# main.net
KiCad netlist of a schematic drawn in EAGLE
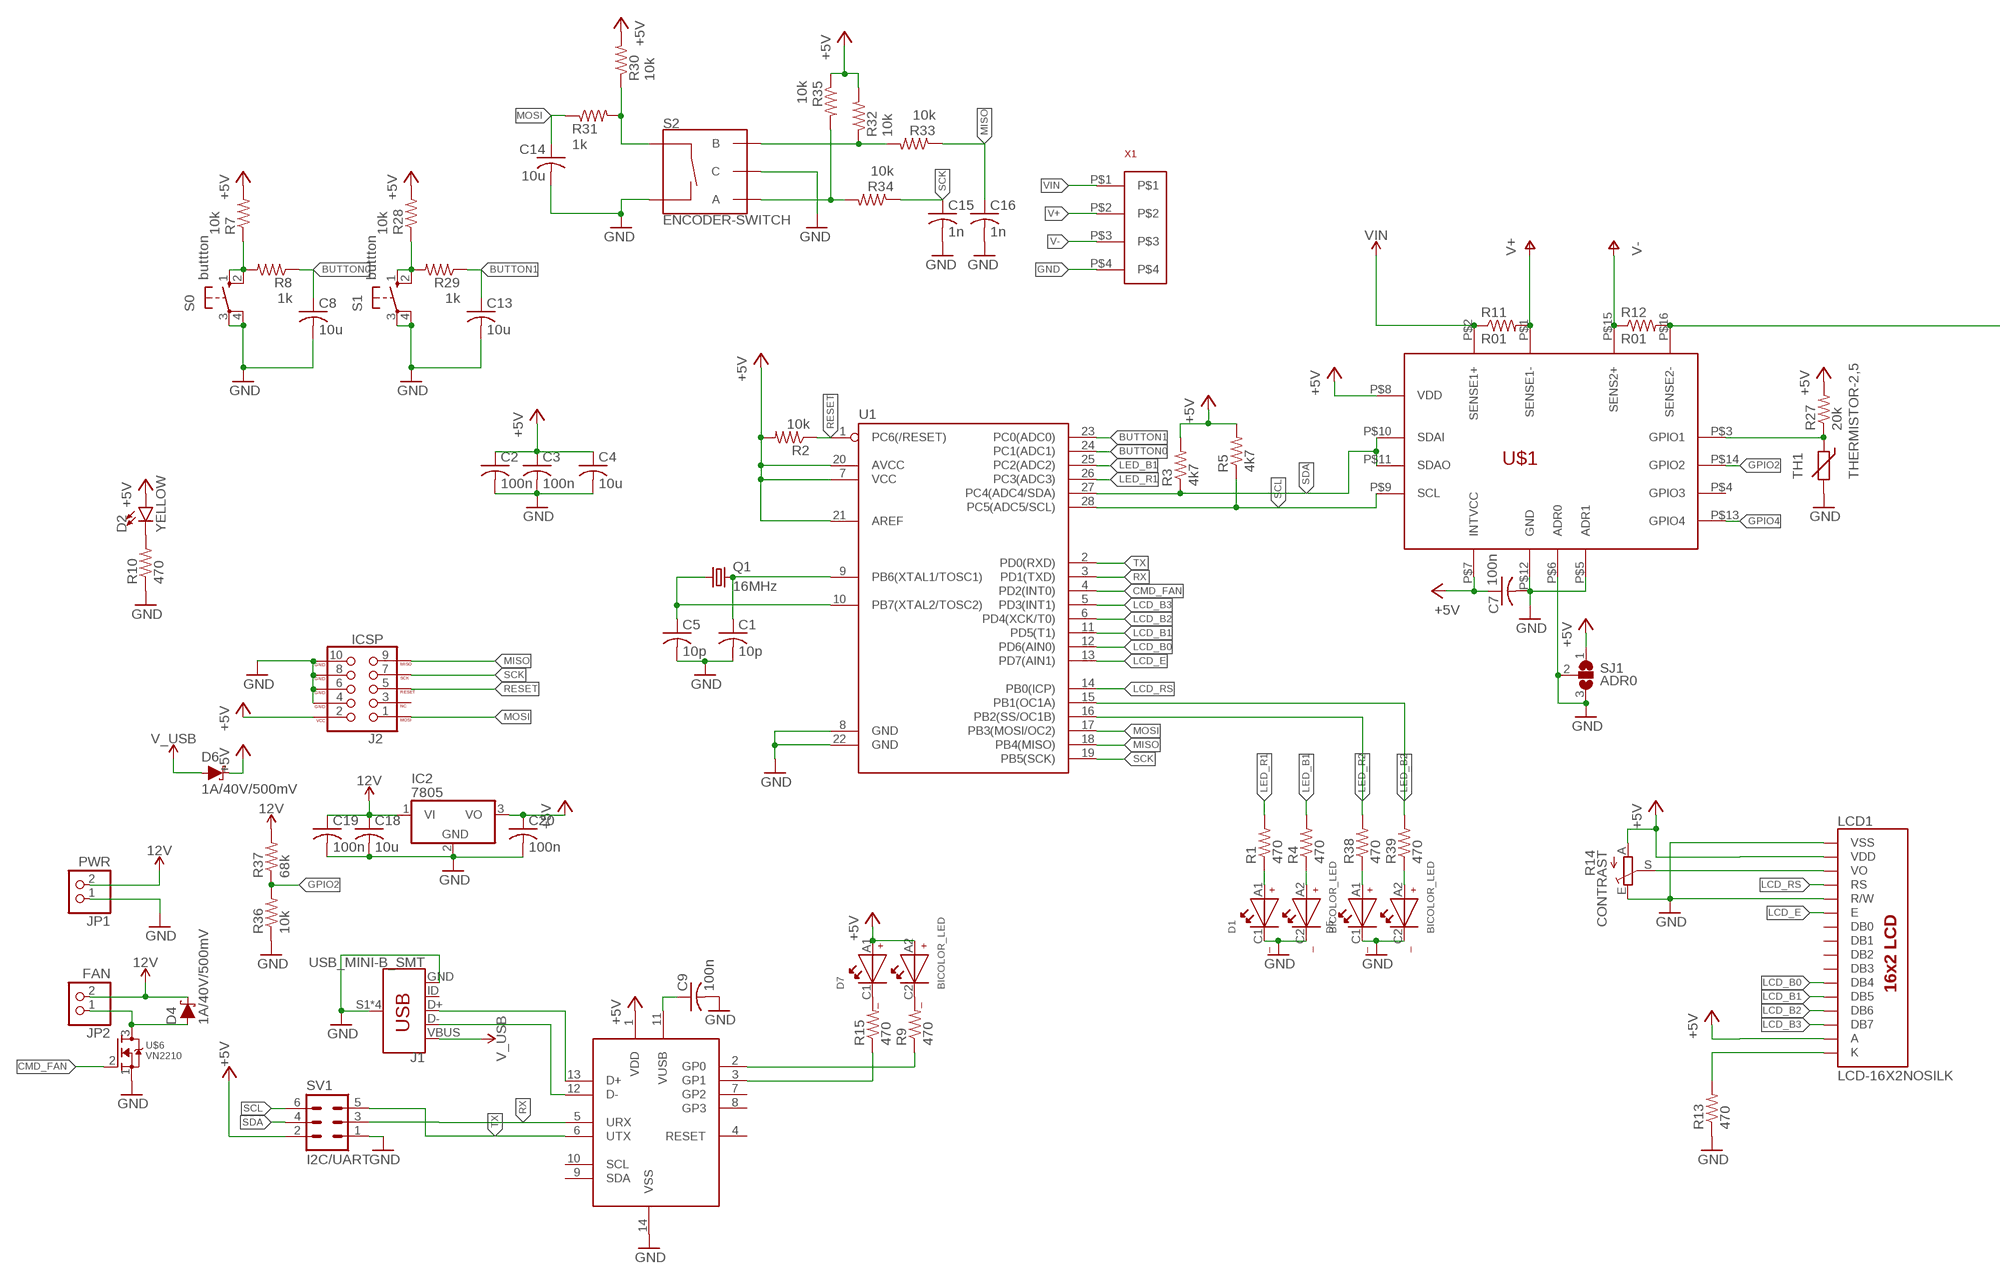
[diagram p0: schematic, sheet 1, part 1 of 2]
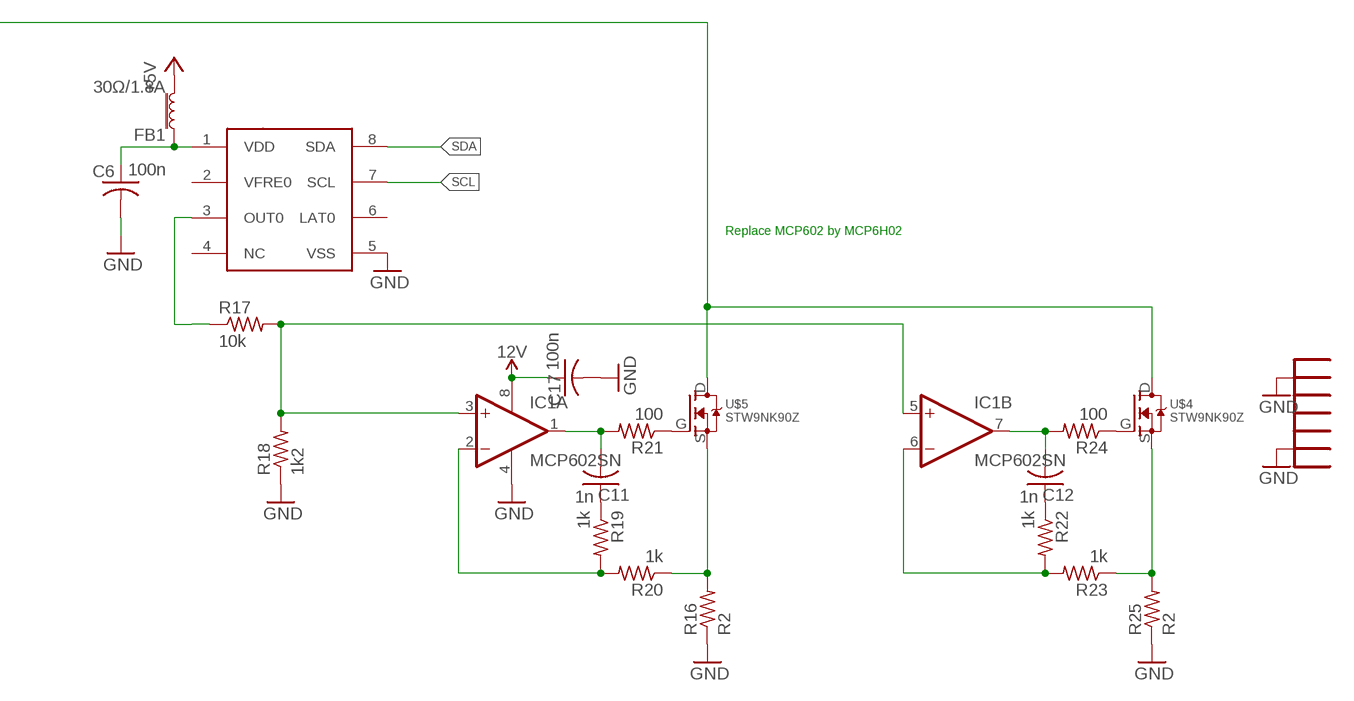
[diagram p1: schematic, sheet 1, part 2 of 2]

(export (version "E")
  (design (tool "Eeschema 10.0.6"))
  (components
    (comp (ref "BR1")
      (value "MCP2221A")
      (footprint "eagle-import:DIP14")
      (libsource (lib "eagle-import") (part "MCP2221A"))
    )
    (comp (ref "C1")
      (value "10p")
      (footprint "eagle-import:C0603")
      (libsource (lib "eagle-import") (part "C-USC0603"))
    )
    (comp (ref "C2")
      (value "100n")
      (footprint "eagle-import:C0603")
      (libsource (lib "eagle-import") (part "C-USC0603"))
    )
    (comp (ref "C3")
      (value "100n")
      (footprint "eagle-import:C0603")
      (libsource (lib "eagle-import") (part "C-USC0603"))
    )
    (comp (ref "C4")
      (value "10u")
      (footprint "eagle-import:C1206")
      (libsource (lib "eagle-import") (part "C-USC1206"))
    )
    (comp (ref "C5")
      (value "10p")
      (footprint "eagle-import:C0603")
      (libsource (lib "eagle-import") (part "C-USC0603"))
    )
    (comp (ref "C6")
      (value "100n")
      (footprint "eagle-import:C0603")
      (libsource (lib "eagle-import") (part "C-USC0603"))
    )
    (comp (ref "C7")
      (value "100n")
      (footprint "eagle-import:C0603")
      (libsource (lib "eagle-import") (part "C-USC0603"))
    )
    (comp (ref "C8")
      (value "10u")
      (footprint "eagle-import:C0603")
      (libsource (lib "eagle-import") (part "C-USC0603"))
    )
    (comp (ref "C9")
      (value "100n")
      (footprint "eagle-import:C0603")
      (libsource (lib "eagle-import") (part "C-USC0603"))
    )
    (comp (ref "C11")
      (value "1n")
      (footprint "eagle-import:C0805")
      (libsource (lib "eagle-import") (part "C-USC0805"))
    )
    (comp (ref "C12")
      (value "1n")
      (footprint "eagle-import:C0805")
      (libsource (lib "eagle-import") (part "C-USC0805"))
    )
    (comp (ref "C13")
      (value "10u")
      (footprint "eagle-import:C0603")
      (libsource (lib "eagle-import") (part "C-USC0603"))
    )
    (comp (ref "C14")
      (value "10u")
      (footprint "eagle-import:C0603")
      (libsource (lib "eagle-import") (part "C-USC0603"))
    )
    (comp (ref "C15")
      (value "1n")
      (footprint "eagle-import:C0603")
      (libsource (lib "eagle-import") (part "C-USC0603"))
    )
    (comp (ref "C16")
      (value "1n")
      (footprint "eagle-import:C0603")
      (libsource (lib "eagle-import") (part "C-USC0603"))
    )
    (comp (ref "C17")
      (value "100n")
      (footprint "eagle-import:C0603")
      (libsource (lib "eagle-import") (part "C-USC0603"))
    )
    (comp (ref "C18")
      (value "10u")
      (footprint "eagle-import:C1206")
      (libsource (lib "eagle-import") (part "C-USC1206"))
    )
    (comp (ref "C19")
      (value "100n")
      (footprint "eagle-import:C0603")
      (libsource (lib "eagle-import") (part "C-USC0603"))
    )
    (comp (ref "C20")
      (value "100n")
      (footprint "eagle-import:C0603")
      (libsource (lib "eagle-import") (part "C-USC0603"))
    )
    (comp (ref "D1")
      (value "BICOLOR_LED")
      (footprint "eagle-import:BICOLOR_LED")
      (libsource (lib "eagle-import") (part "BICOLOR_LED"))
    )
    (comp (ref "D2")
      (value "YELLOW")
      (footprint "eagle-import:LED_3MM")
      (libsource (lib "eagle-import") (part "LED3MM"))
    )
    (comp (ref "D4")
      (value "1A/40V/500mV")
      (footprint "eagle-import:SMA-DIODE")
      (libsource (lib "eagle-import") (part "DIODE-SCHOTTKY-SS14"))
    )
    (comp (ref "D5")
      (value "BICOLOR_LED")
      (footprint "eagle-import:BICOLOR_LED")
      (libsource (lib "eagle-import") (part "BICOLOR_LED"))
    )
    (comp (ref "D6")
      (value "1A/40V/500mV")
      (footprint "eagle-import:SMA-DIODE")
      (libsource (lib "eagle-import") (part "DIODE-SCHOTTKY-SS14"))
    )
    (comp (ref "D7")
      (value "BICOLOR_LED")
      (footprint "eagle-import:BICOLOR_LED")
      (libsource (lib "eagle-import") (part "BICOLOR_LED"))
    )
    (comp (ref "FB1")
      (value "30Ω/1.8A")
      (footprint "eagle-import:0603")
      (libsource (lib "eagle-import") (part "FERRITE_BEAD-0603"))
    )
    (comp (ref "IC1")
      (value "MCP602SN")
      (footprint "eagle-import:SO08")
      (libsource (lib "eagle-import") (part "MCP602SN"))
    )
    (comp (ref "IC2")
      (value "7805")
      (footprint "eagle-import:TO220V")
      (libsource (lib "eagle-import") (part "78TV6"))
    )
    (comp (ref "J1")
      (value "USB_MINI-B_SMT")
      (footprint "eagle-import:USB-MINIB")
      (libsource (lib "eagle-import") (part "USB_MINI-B_SMT"))
    )
    (comp (ref "J2")
      (value "ICSP")
      (footprint "eagle-import:2X5-SHROUDED")
      (libsource (lib "eagle-import") (part "AVR_SPI_PROG_5X2PTH2"))
    )
    (comp (ref "JP1")
      (value "PWR")
      (footprint "eagle-import:1X02")
      (libsource (lib "eagle-import") (part "PINHD-1X2"))
    )
    (comp (ref "JP2")
      (value "FAN")
      (footprint "eagle-import:1X02")
      (libsource (lib "eagle-import") (part "PINHD-1X2"))
    )
    (comp (ref "LCD1")
      (value "LCD-16X2NOSILK")
      (footprint "eagle-import:LCD-16X2_NOSILK")
      (libsource (lib "eagle-import") (part "LCD-16X2NOSILK"))
    )
    (comp (ref "Q1")
      (value "16MHz")
      (footprint "eagle-import:HC49U70")
      (libsource (lib "eagle-import") (part "CRYSTALHC49U70"))
    )
    (comp (ref "R1")
      (value "470")
      (footprint "eagle-import:R0805")
      (libsource (lib "eagle-import") (part "R-US_R0805"))
    )
    (comp (ref "R2")
      (value "10k")
      (footprint "eagle-import:R0805")
      (libsource (lib "eagle-import") (part "R-US_R0805"))
    )
    (comp (ref "R3")
      (value "4k7")
      (footprint "eagle-import:R0805")
      (libsource (lib "eagle-import") (part "R-US_R0805"))
    )
    (comp (ref "R4")
      (value "470")
      (footprint "eagle-import:R0805")
      (libsource (lib "eagle-import") (part "R-US_R0805"))
    )
    (comp (ref "R5")
      (value "4k7")
      (footprint "eagle-import:R0805")
      (libsource (lib "eagle-import") (part "R-US_R0805"))
    )
    (comp (ref "R7")
      (value "10k")
      (footprint "eagle-import:R0805")
      (libsource (lib "eagle-import") (part "R-US_R0805"))
    )
    (comp (ref "R8")
      (value "1k")
      (footprint "eagle-import:R0805")
      (libsource (lib "eagle-import") (part "R-US_R0805"))
    )
    (comp (ref "R9")
      (value "470")
      (footprint "eagle-import:R0805")
      (libsource (lib "eagle-import") (part "R-US_R0805"))
    )
    (comp (ref "R10")
      (value "470")
      (footprint "eagle-import:R0805")
      (libsource (lib "eagle-import") (part "R-US_R0805"))
    )
    (comp (ref "R11")
      (value "R01")
      (footprint "eagle-import:R2512")
      (libsource (lib "eagle-import") (part "R-US_R2512"))
    )
    (comp (ref "R12")
      (value "R01")
      (footprint "eagle-import:R2512")
      (libsource (lib "eagle-import") (part "R-US_R2512"))
    )
    (comp (ref "R13")
      (value "470")
      (footprint "eagle-import:R0805")
      (libsource (lib "eagle-import") (part "R-US_R0805"))
    )
    (comp (ref "R14")
      (value "CONTRAST")
      (footprint "eagle-import:RJ9W")
      (libsource (lib "eagle-import") (part "TRIM_EU-RJ9W"))
    )
    (comp (ref "R15")
      (value "470")
      (footprint "eagle-import:R0805")
      (libsource (lib "eagle-import") (part "R-US_R0805"))
    )
    (comp (ref "R16")
      (value "R2")
      (footprint "eagle-import:R2512")
      (libsource (lib "eagle-import") (part "R-US_R2512"))
    )
    (comp (ref "R17")
      (value "10k")
      (footprint "eagle-import:R0805")
      (libsource (lib "eagle-import") (part "R-US_R0805"))
    )
    (comp (ref "R18")
      (value "1k2")
      (footprint "eagle-import:R0805")
      (libsource (lib "eagle-import") (part "R-US_R0805"))
    )
    (comp (ref "R19")
      (value "1k")
      (footprint "eagle-import:R0805")
      (libsource (lib "eagle-import") (part "R-US_R0805"))
    )
    (comp (ref "R20")
      (value "1k")
      (footprint "eagle-import:R0805")
      (libsource (lib "eagle-import") (part "R-US_R0805"))
    )
    (comp (ref "R21")
      (value "100")
      (footprint "eagle-import:R0805")
      (libsource (lib "eagle-import") (part "R-US_R0805"))
    )
    (comp (ref "R22")
      (value "1k")
      (footprint "eagle-import:R0805")
      (libsource (lib "eagle-import") (part "R-US_R0805"))
    )
    (comp (ref "R23")
      (value "1k")
      (footprint "eagle-import:R0805")
      (libsource (lib "eagle-import") (part "R-US_R0805"))
    )
    (comp (ref "R24")
      (value "100")
      (footprint "eagle-import:R0805")
      (libsource (lib "eagle-import") (part "R-US_R0805"))
    )
    (comp (ref "R25")
      (value "R2")
      (footprint "eagle-import:R2512")
      (libsource (lib "eagle-import") (part "R-US_R2512"))
    )
    (comp (ref "R27")
      (value "20k")
      (footprint "eagle-import:R0805")
      (libsource (lib "eagle-import") (part "R-US_R0805"))
    )
    (comp (ref "R28")
      (value "10k")
      (footprint "eagle-import:R0805")
      (libsource (lib "eagle-import") (part "R-US_R0805"))
    )
    (comp (ref "R29")
      (value "1k")
      (footprint "eagle-import:R0805")
      (libsource (lib "eagle-import") (part "R-US_R0805"))
    )
    (comp (ref "R30")
      (value "10k")
      (footprint "eagle-import:R0805")
      (libsource (lib "eagle-import") (part "R-US_R0805"))
    )
    (comp (ref "R31")
      (value "1k")
      (footprint "eagle-import:R0805")
      (libsource (lib "eagle-import") (part "R-US_R0805"))
    )
    (comp (ref "R32")
      (value "10k")
      (footprint "eagle-import:R0805")
      (libsource (lib "eagle-import") (part "R-US_R0805"))
    )
    (comp (ref "R33")
      (value "10k")
      (footprint "eagle-import:R0805")
      (libsource (lib "eagle-import") (part "R-US_R0805"))
    )
    (comp (ref "R34")
      (value "10k")
      (footprint "eagle-import:R0805")
      (libsource (lib "eagle-import") (part "R-US_R0805"))
    )
    (comp (ref "R35")
      (value "10k")
      (footprint "eagle-import:R0805")
      (libsource (lib "eagle-import") (part "R-US_R0805"))
    )
    (comp (ref "R36")
      (value "10k")
      (footprint "eagle-import:R0805")
      (libsource (lib "eagle-import") (part "R-US_R0805"))
    )
    (comp (ref "R37")
      (value "68k")
      (footprint "eagle-import:R0805")
      (libsource (lib "eagle-import") (part "R-US_R0805"))
    )
    (comp (ref "R38")
      (value "470")
      (footprint "eagle-import:R0805")
      (libsource (lib "eagle-import") (part "R-US_R0805"))
    )
    (comp (ref "R39")
      (value "470")
      (footprint "eagle-import:R0805")
      (libsource (lib "eagle-import") (part "R-US_R0805"))
    )
    (comp (ref "S0")
      (value "buttton")
      (footprint "eagle-import:B3F-10XX")
      (fields (field (name "MPN") "B3F-1000"))
      (libsource (lib "eagle-import") (part "10-XX"))
    )
    (comp (ref "S1")
      (value "buttton")
      (footprint "eagle-import:B3F-10XX")
      (fields (field (name "MPN") "B3F-1000"))
      (libsource (lib "eagle-import") (part "10-XX"))
    )
    (comp (ref "S2")
      (value "ENCODER-SWITCH")
      (footprint "eagle-import:ROTARY_ENC_PLAIN")
      (libsource (lib "eagle-import") (part "ENCODER-SWITCH"))
    )
    (comp (ref "SJ1")
      (value "ADR0")
      (footprint "eagle-import:SJ_2")
      (libsource (lib "eagle-import") (part "SJ2W"))
    )
    (comp (ref "SV1")
      (value "I2C/UART")
      (footprint "eagle-import:MA03-2")
      (libsource (lib "eagle-import") (part "MA03-2"))
    )
    (comp (ref "TH1")
      (value "THERMISTOR-2,5")
      (footprint "eagle-import:RS-2,5")
      (libsource (lib "eagle-import") (part "THERMISTOR-2,5"))
    )
    (comp (ref "U$1")
      (value "LTC2992")
      (footprint "eagle-import:MSOP16")
      (libsource (lib "eagle-import") (part "LTC2992"))
    )
    (comp (ref "U$2")
      (value "HEATSINK_0NOSILK")
      (footprint "eagle-import:HEATSINK_01")
      (libsource (lib "eagle-import") (part "HEATSINK_0NOSILK"))
    )
    (comp (ref "U$3")
      (value "MCP47FEB21")
      (footprint "eagle-import:TSSOP8")
      (libsource (lib "eagle-import") (part "MCP47FEB21"))
    )
    (comp (ref "U$4")
      (value "STW9NK90Z")
      (footprint "eagle-import:TO247BV")
      (libsource (lib "eagle-import") (part "STW9NK90Z"))
    )
    (comp (ref "U$5")
      (value "STW9NK90Z")
      (footprint "eagle-import:TO247BV")
      (libsource (lib "eagle-import") (part "STW9NK90Z"))
    )
    (comp (ref "U$6")
      (value "VN2210")
      (footprint "eagle-import:TO92")
      (libsource (lib "eagle-import") (part "VN2210"))
    )
    (comp (ref "U1")
      (value "328P")
      (footprint "eagle-import:DIP28")
      (libsource (lib "eagle-import") (part "ATMEGA328P_PDIP"))
    )
    (comp (ref "X1")
      (value "SCREWTERM_5MM_4WAY")
      (footprint "eagle-import:SCREWTERM_5MM_4WAY")
      (libsource (lib "eagle-import") (part "SCREWTERM_5MM_4WAY"))
    )
  )
  (nets
    (net (code "1") (name "+5V") (class "Default")
      (node (ref "BR1") (pin "1") (pinfunction "VDD_1") (pintype "bidirectional"))
      (node (ref "C2") (pin "1") (pinfunction "1_1") (pintype "passive"))
      (node (ref "C20") (pin "1") (pinfunction "1_1") (pintype "passive"))
      (node (ref "C3") (pin "1") (pinfunction "1_1") (pintype "passive"))
      (node (ref "C4") (pin "1") (pinfunction "1_1") (pintype "passive"))
      (node (ref "C7") (pin "1") (pinfunction "1_1") (pintype "passive"))
      (node (ref "D2") (pin "A") (pinfunction "A_A") (pintype "passive"))
      (node (ref "D6") (pin "C") (pinfunction "C_C") (pintype "passive"))
      (node (ref "D7") (pin "A1") (pinfunction "A1_A1") (pintype "passive"))
      (node (ref "D7") (pin "A2") (pinfunction "A2_A2") (pintype "passive"))
      (node (ref "FB1") (pin "2") (pinfunction "2_2") (pintype "passive"))
      (node (ref "IC2") (pin "3") (pinfunction "VO_3") (pintype "passive"))
      (node (ref "J2") (pin "2") (pinfunction "VCC_2") (pintype "power_in"))
      (node (ref "LCD1") (pin "15") (pinfunction "A_15") (pintype "power_in"))
      (node (ref "LCD1") (pin "2") (pinfunction "VDD_2") (pintype "power_in"))
      (node (ref "R14") (pin "A") (pinfunction "A_A") (pintype "passive"))
      (node (ref "R2") (pin "2") (pinfunction "2_2") (pintype "passive"))
      (node (ref "R27") (pin "2") (pinfunction "2_2") (pintype "passive"))
      (node (ref "R28") (pin "2") (pinfunction "2_2") (pintype "passive"))
      (node (ref "R3") (pin "2") (pinfunction "2_2") (pintype "passive"))
      (node (ref "R30") (pin "2") (pinfunction "2_2") (pintype "passive"))
      (node (ref "R32") (pin "2") (pinfunction "2_2") (pintype "passive"))
      (node (ref "R35") (pin "1") (pinfunction "1_1") (pintype "passive"))
      (node (ref "R5") (pin "2") (pinfunction "2_2") (pintype "passive"))
      (node (ref "R7") (pin "2") (pinfunction "2_2") (pintype "passive"))
      (node (ref "SJ1") (pin "1") (pinfunction "1_1") (pintype "passive"))
      (node (ref "SV1") (pin "2") (pinfunction "2_2") (pintype "passive"))
      (node (ref "U$1") (pin "P$7") (pinfunction "INTVCC_P$7") (pintype "bidirectional"))
      (node (ref "U$1") (pin "P$8") (pinfunction "VDD_P$8") (pintype "bidirectional"))
      (node (ref "U1") (pin "20") (pinfunction "AVCC_20") (pintype "bidirectional"))
      (node (ref "U1") (pin "21") (pinfunction "AREF_21") (pintype "bidirectional"))
      (node (ref "U1") (pin "7") (pinfunction "VCC_7") (pintype "bidirectional"))
    )
    (net (code "2") (name "12V") (class "Default")
      (node (ref "C17") (pin "1") (pinfunction "1_1") (pintype "passive"))
      (node (ref "C18") (pin "1") (pinfunction "1_1") (pintype "passive"))
      (node (ref "C19") (pin "1") (pinfunction "1_1") (pintype "passive"))
      (node (ref "D4") (pin "C") (pinfunction "C_C") (pintype "passive"))
      (node (ref "IC1") (pin "8") (pinfunction "V+_8") (pintype "power_in"))
      (node (ref "IC2") (pin "1") (pinfunction "VI_1") (pintype "input"))
      (node (ref "JP1") (pin "2") (pinfunction "2_2") (pintype "passive"))
      (node (ref "JP2") (pin "2") (pinfunction "2_2") (pintype "passive"))
      (node (ref "R37") (pin "2") (pinfunction "2_2") (pintype "passive"))
    )
    (net (code "3") (name "BUTTON0") (class "Default")
      (node (ref "C8") (pin "1") (pinfunction "1_1") (pintype "passive"))
      (node (ref "R8") (pin "1") (pinfunction "1_1") (pintype "passive"))
      (node (ref "U1") (pin "24") (pinfunction "PC1(ADC1)_24") (pintype "bidirectional"))
    )
    (net (code "4") (name "BUTTON1") (class "Default")
      (node (ref "C13") (pin "1") (pinfunction "1_1") (pintype "passive"))
      (node (ref "R29") (pin "1") (pinfunction "1_1") (pintype "passive"))
      (node (ref "U1") (pin "23") (pinfunction "PC0(ADC0)_23") (pintype "bidirectional"))
    )
    (net (code "5") (name "CMD_FAN") (class "Default")
      (node (ref "U$6") (pin "2") (pinfunction "G_2") (pintype "bidirectional"))
      (node (ref "U1") (pin "4") (pinfunction "PD2(INT0)_4") (pintype "bidirectional"))
    )
    (net (code "6") (name "GND") (class "Default")
      (node (ref "BR1") (pin "14") (pinfunction "VSS_14") (pintype "bidirectional"))
      (node (ref "C1") (pin "2") (pinfunction "2_2") (pintype "passive"))
      (node (ref "C13") (pin "2") (pinfunction "2_2") (pintype "passive"))
      (node (ref "C14") (pin "2") (pinfunction "2_2") (pintype "passive"))
      (node (ref "C15") (pin "2") (pinfunction "2_2") (pintype "passive"))
      (node (ref "C16") (pin "2") (pinfunction "2_2") (pintype "passive"))
      (node (ref "C17") (pin "2") (pinfunction "2_2") (pintype "passive"))
      (node (ref "C18") (pin "2") (pinfunction "2_2") (pintype "passive"))
      (node (ref "C19") (pin "2") (pinfunction "2_2") (pintype "passive"))
      (node (ref "C2") (pin "2") (pinfunction "2_2") (pintype "passive"))
      (node (ref "C20") (pin "2") (pinfunction "2_2") (pintype "passive"))
      (node (ref "C3") (pin "2") (pinfunction "2_2") (pintype "passive"))
      (node (ref "C4") (pin "2") (pinfunction "2_2") (pintype "passive"))
      (node (ref "C5") (pin "2") (pinfunction "2_2") (pintype "passive"))
      (node (ref "C6") (pin "2") (pinfunction "2_2") (pintype "passive"))
      (node (ref "C7") (pin "2") (pinfunction "2_2") (pintype "passive"))
      (node (ref "C8") (pin "2") (pinfunction "2_2") (pintype "passive"))
      (node (ref "C9") (pin "2") (pinfunction "2_2") (pintype "passive"))
      (node (ref "D1") (pin "C1") (pinfunction "C1_C1") (pintype "passive"))
      (node (ref "D1") (pin "C2") (pinfunction "C2_C2") (pintype "passive"))
      (node (ref "D5") (pin "C1") (pinfunction "C1_C1") (pintype "passive"))
      (node (ref "D5") (pin "C2") (pinfunction "C2_C2") (pintype "passive"))
      (node (ref "IC1") (pin "4") (pinfunction "V-_4") (pintype "power_in"))
      (node (ref "IC2") (pin "2") (pinfunction "GND_2") (pintype "passive"))
      (node (ref "J1") (pin "GND") (pinfunction "GND_GND") (pintype "power_in"))
      (node (ref "J1") (pin "S1") (pinfunction "SHIELD_S1") (pintype "bidirectional"))
      (node (ref "J1") (pin "S2") (pinfunction "SHIELD_S2") (pintype "bidirectional"))
      (node (ref "J1") (pin "S3") (pinfunction "SHIELD_S3") (pintype "bidirectional"))
      (node (ref "J1") (pin "S4") (pinfunction "SHIELD_S4") (pintype "bidirectional"))
      (node (ref "J2") (pin "10") (pinfunction "GND_10") (pintype "power_in"))
      (node (ref "J2") (pin "4") (pinfunction "GND_4") (pintype "power_in"))
      (node (ref "J2") (pin "6") (pinfunction "GND_6") (pintype "power_in"))
      (node (ref "J2") (pin "8") (pinfunction "GND_8") (pintype "power_in"))
      (node (ref "JP1") (pin "1") (pinfunction "1_1") (pintype "passive"))
      (node (ref "LCD1") (pin "1") (pinfunction "VSS_1") (pintype "power_in"))
      (node (ref "LCD1") (pin "5") (pinfunction "R/W_5") (pintype "input"))
      (node (ref "R10") (pin "1") (pinfunction "1_1") (pintype "passive"))
      (node (ref "R13") (pin "1") (pinfunction "1_1") (pintype "passive"))
      (node (ref "R14") (pin "E") (pinfunction "E_E") (pintype "passive"))
      (node (ref "R16") (pin "1") (pinfunction "1_1") (pintype "passive"))
      (node (ref "R18") (pin "1") (pinfunction "1_1") (pintype "passive"))
      (node (ref "R25") (pin "1") (pinfunction "1_1") (pintype "passive"))
      (node (ref "R36") (pin "1") (pinfunction "1_1") (pintype "passive"))
      (node (ref "S0") (pin "3") (pinfunction "P_3") (pintype "passive"))
      (node (ref "S0") (pin "4") (pinfunction "P1_4") (pintype "passive"))
      (node (ref "S1") (pin "3") (pinfunction "P_3") (pintype "passive"))
      (node (ref "S1") (pin "4") (pinfunction "P1_4") (pintype "passive"))
      (node (ref "S2") (pin "C") (pinfunction "C_C") (pintype "bidirectional"))
      (node (ref "S2") (pin "SW-") (pinfunction "SW-_SW-") (pintype "bidirectional"))
      (node (ref "SJ1") (pin "2") (pinfunction "2_2") (pintype "passive"))
      (node (ref "SJ1") (pin "3") (pinfunction "3_3") (pintype "passive"))
      (node (ref "SV1") (pin "1") (pinfunction "1_1") (pintype "passive"))
      (node (ref "TH1") (pin "2") (pinfunction "2_2") (pintype "passive"))
      (node (ref "U$1") (pin "P$12") (pinfunction "GND_P$12") (pintype "bidirectional"))
      (node (ref "U$1") (pin "P$5") (pinfunction "ADR1_P$5") (pintype "bidirectional"))
      (node (ref "U$1") (pin "P$6") (pinfunction "ADR0_P$6") (pintype "bidirectional"))
      (node (ref "U$2") (pin "P$1") (pinfunction "P$1_P$1") (pintype "bidirectional"))
      (node (ref "U$2") (pin "P$2") (pinfunction "P$2_P$2") (pintype "bidirectional"))
      (node (ref "U$3") (pin "5") (pinfunction "VSS_5") (pintype "bidirectional"))
      (node (ref "U$6") (pin "1") (pinfunction "S_1") (pintype "bidirectional"))
      (node (ref "U1") (pin "22") (pinfunction "GND_22") (pintype "bidirectional"))
      (node (ref "U1") (pin "8") (pinfunction "GND_8") (pintype "bidirectional"))
      (node (ref "X1") (pin "P$4") (pinfunction "P$4_P$4") (pintype "bidirectional"))
    )
    (net (code "7") (name "GPIO2") (class "Default")
      (node (ref "R36") (pin "2") (pinfunction "2_2") (pintype "passive"))
      (node (ref "R37") (pin "1") (pinfunction "1_1") (pintype "passive"))
      (node (ref "U$1") (pin "P$14") (pinfunction "GPIO2_P$14") (pintype "bidirectional"))
    )
    (net (code "8") (name "GPIO4") (class "Default")
      (node (ref "U$1") (pin "P$13") (pinfunction "GPIO4_P$13") (pintype "bidirectional"))
    )
    (net (code "9") (name "LCD_B0") (class "Default")
      (node (ref "LCD1") (pin "11") (pinfunction "DB4_11") (pintype "bidirectional"))
      (node (ref "U1") (pin "12") (pinfunction "PD6(AIN0)_12") (pintype "bidirectional"))
    )
    (net (code "10") (name "LCD_B1") (class "Default")
      (node (ref "LCD1") (pin "12") (pinfunction "DB5_12") (pintype "bidirectional"))
      (node (ref "U1") (pin "11") (pinfunction "PD5(T1)_11") (pintype "bidirectional"))
    )
    (net (code "11") (name "LCD_B2") (class "Default")
      (node (ref "LCD1") (pin "13") (pinfunction "DB6_13") (pintype "bidirectional"))
      (node (ref "U1") (pin "6") (pinfunction "PD4(XCK/T0)_6") (pintype "bidirectional"))
    )
    (net (code "12") (name "LCD_B3") (class "Default")
      (node (ref "LCD1") (pin "14") (pinfunction "DB7_14") (pintype "bidirectional"))
      (node (ref "U1") (pin "5") (pinfunction "PD3(INT1)_5") (pintype "bidirectional"))
    )
    (net (code "13") (name "LCD_E") (class "Default")
      (node (ref "LCD1") (pin "6") (pinfunction "E_6") (pintype "input"))
      (node (ref "U1") (pin "13") (pinfunction "PD7(AIN1)_13") (pintype "bidirectional"))
    )
    (net (code "14") (name "LCD_RS") (class "Default")
      (node (ref "LCD1") (pin "4") (pinfunction "RS_4") (pintype "input"))
      (node (ref "U1") (pin "14") (pinfunction "PB0(ICP)_14") (pintype "bidirectional"))
    )
    (net (code "15") (name "LED_B1") (class "Default")
      (node (ref "R4") (pin "2") (pinfunction "2_2") (pintype "passive"))
      (node (ref "U1") (pin "25") (pinfunction "PC2(ADC2)_25") (pintype "bidirectional"))
    )
    (net (code "16") (name "LED_B2") (class "Default")
      (node (ref "R39") (pin "2") (pinfunction "2_2") (pintype "passive"))
      (node (ref "U1") (pin "15") (pinfunction "PB1(OC1A)_15") (pintype "bidirectional"))
    )
    (net (code "17") (name "LED_R1") (class "Default")
      (node (ref "R1") (pin "2") (pinfunction "2_2") (pintype "passive"))
      (node (ref "U1") (pin "26") (pinfunction "PC3(ADC3)_26") (pintype "bidirectional"))
    )
    (net (code "18") (name "LED_R2") (class "Default")
      (node (ref "R38") (pin "2") (pinfunction "2_2") (pintype "passive"))
      (node (ref "U1") (pin "16") (pinfunction "PB2(SS/OC1B)_16") (pintype "bidirectional"))
    )
    (net (code "19") (name "MISO") (class "Default")
      (node (ref "C16") (pin "1") (pinfunction "1_1") (pintype "passive"))
      (node (ref "J2") (pin "9") (pinfunction "MISO_9") (pintype "passive"))
      (node (ref "R33") (pin "1") (pinfunction "1_1") (pintype "passive"))
      (node (ref "U1") (pin "18") (pinfunction "PB4(MISO)_18") (pintype "bidirectional"))
    )
    (net (code "20") (name "MOSI") (class "Default")
      (node (ref "C14") (pin "1") (pinfunction "1_1") (pintype "passive"))
      (node (ref "J2") (pin "1") (pinfunction "MOSI_1") (pintype "passive"))
      (node (ref "R31") (pin "1") (pinfunction "1_1") (pintype "passive"))
      (node (ref "U1") (pin "17") (pinfunction "PB3(MOSI/OC2)_17") (pintype "bidirectional"))
    )
    (net (code "21") (name "Net-(BR1-D+)") (class "Default")
      (node (ref "BR1") (pin "13") (pinfunction "D+_13") (pintype "bidirectional"))
      (node (ref "J1") (pin "D+") (pinfunction "D+_D+") (pintype "bidirectional"))
    )
    (net (code "22") (name "Net-(BR1-D-)") (class "Default")
      (node (ref "BR1") (pin "12") (pinfunction "D-_12") (pintype "bidirectional"))
      (node (ref "J1") (pin "D-") (pinfunction "D-_D-") (pintype "bidirectional"))
    )
    (net (code "23") (name "Net-(BR1-GP0)") (class "Default")
      (node (ref "BR1") (pin "2") (pinfunction "GP0_2") (pintype "bidirectional"))
      (node (ref "R9") (pin "1") (pinfunction "1_1") (pintype "passive"))
    )
    (net (code "24") (name "Net-(BR1-GP1)") (class "Default")
      (node (ref "BR1") (pin "3") (pinfunction "GP1_3") (pintype "bidirectional"))
      (node (ref "R15") (pin "1") (pinfunction "1_1") (pintype "passive"))
    )
    (net (code "25") (name "Net-(BR1-VUSB)") (class "Default")
      (node (ref "BR1") (pin "11") (pinfunction "VUSB_11") (pintype "bidirectional"))
      (node (ref "C9") (pin "1") (pinfunction "1_1") (pintype "passive"))
    )
    (net (code "26") (name "Net-(C11-Pad1)") (class "Default")
      (node (ref "C11") (pin "1") (pinfunction "1_1") (pintype "passive"))
      (node (ref "R19") (pin "1") (pinfunction "1_1") (pintype "passive"))
    )
    (net (code "27") (name "Net-(C12-Pad1)") (class "Default")
      (node (ref "C12") (pin "1") (pinfunction "1_1") (pintype "passive"))
      (node (ref "R22") (pin "1") (pinfunction "1_1") (pintype "passive"))
    )
    (net (code "28") (name "Net-(D1-PadA1)") (class "Default")
      (node (ref "D1") (pin "A1") (pinfunction "A1_A1") (pintype "passive"))
      (node (ref "R1") (pin "1") (pinfunction "1_1") (pintype "passive"))
    )
    (net (code "29") (name "Net-(D1-PadA2)") (class "Default")
      (node (ref "D1") (pin "A2") (pinfunction "A2_A2") (pintype "passive"))
      (node (ref "R4") (pin "1") (pinfunction "1_1") (pintype "passive"))
    )
    (net (code "30") (name "Net-(D2-C)") (class "Default")
      (node (ref "D2") (pin "K") (pinfunction "C_K") (pintype "passive"))
      (node (ref "R10") (pin "2") (pinfunction "2_2") (pintype "passive"))
    )
    (net (code "31") (name "Net-(D5-PadA1)") (class "Default")
      (node (ref "D5") (pin "A1") (pinfunction "A1_A1") (pintype "passive"))
      (node (ref "R38") (pin "1") (pinfunction "1_1") (pintype "passive"))
    )
    (net (code "32") (name "Net-(D5-PadA2)") (class "Default")
      (node (ref "D5") (pin "A2") (pinfunction "A2_A2") (pintype "passive"))
      (node (ref "R39") (pin "1") (pinfunction "1_1") (pintype "passive"))
    )
    (net (code "33") (name "Net-(D7-PadC1)") (class "Default")
      (node (ref "D7") (pin "C1") (pinfunction "C1_C1") (pintype "passive"))
      (node (ref "R15") (pin "2") (pinfunction "2_2") (pintype "passive"))
    )
    (net (code "34") (name "Net-(D7-PadC2)") (class "Default")
      (node (ref "D7") (pin "C2") (pinfunction "C2_C2") (pintype "passive"))
      (node (ref "R9") (pin "2") (pinfunction "2_2") (pintype "passive"))
    )
    (net (code "35") (name "Net-(IC1A-+IN)") (class "Default")
      (node (ref "IC1") (pin "3") (pinfunction "+IN_3") (pintype "input"))
      (node (ref "IC1") (pin "5") (pinfunction "+IN_5") (pintype "input"))
      (node (ref "R17") (pin "2") (pinfunction "2_2") (pintype "passive"))
      (node (ref "R18") (pin "2") (pinfunction "2_2") (pintype "passive"))
    )
    (net (code "36") (name "Net-(IC1A--IN)") (class "Default")
      (node (ref "IC1") (pin "2") (pinfunction "-IN_2") (pintype "input"))
      (node (ref "R19") (pin "2") (pinfunction "2_2") (pintype "passive"))
      (node (ref "R20") (pin "2") (pinfunction "2_2") (pintype "passive"))
    )
    (net (code "37") (name "Net-(IC1A-OUT)") (class "Default")
      (node (ref "C11") (pin "2") (pinfunction "2_2") (pintype "passive"))
      (node (ref "IC1") (pin "1") (pinfunction "OUT_1") (pintype "output"))
      (node (ref "R21") (pin "2") (pinfunction "2_2") (pintype "passive"))
    )
    (net (code "38") (name "Net-(IC1B--IN)") (class "Default")
      (node (ref "IC1") (pin "6") (pinfunction "-IN_6") (pintype "input"))
      (node (ref "R22") (pin "2") (pinfunction "2_2") (pintype "passive"))
      (node (ref "R23") (pin "2") (pinfunction "2_2") (pintype "passive"))
    )
    (net (code "39") (name "Net-(IC1B-OUT)") (class "Default")
      (node (ref "C12") (pin "2") (pinfunction "2_2") (pintype "passive"))
      (node (ref "IC1") (pin "7") (pinfunction "OUT_7") (pintype "output"))
      (node (ref "R24") (pin "2") (pinfunction "2_2") (pintype "passive"))
    )
    (net (code "40") (name "Net-(LCD1-K)") (class "Default")
      (node (ref "LCD1") (pin "16") (pinfunction "K_16") (pintype "power_in"))
      (node (ref "R13") (pin "2") (pinfunction "2_2") (pintype "passive"))
    )
    (net (code "41") (name "Net-(LCD1-VO)") (class "Default")
      (node (ref "LCD1") (pin "3") (pinfunction "VO_3") (pintype "bidirectional"))
      (node (ref "R14") (pin "S") (pinfunction "S_S") (pintype "passive"))
    )
    (net (code "42") (name "Net-(R16-Pad2)") (class "Default")
      (node (ref "R16") (pin "2") (pinfunction "2_2") (pintype "passive"))
      (node (ref "R20") (pin "1") (pinfunction "1_1") (pintype "passive"))
      (node (ref "U$5") (pin "S") (pinfunction "S_S") (pintype "bidirectional"))
    )
    (net (code "43") (name "Net-(R21-Pad1)") (class "Default")
      (node (ref "R21") (pin "1") (pinfunction "1_1") (pintype "passive"))
      (node (ref "U$5") (pin "G") (pinfunction "G_G") (pintype "bidirectional"))
    )
    (net (code "44") (name "Net-(R23-Pad1)") (class "Default")
      (node (ref "R23") (pin "1") (pinfunction "1_1") (pintype "passive"))
      (node (ref "R25") (pin "2") (pinfunction "2_2") (pintype "passive"))
      (node (ref "U$4") (pin "S") (pinfunction "S_S") (pintype "bidirectional"))
    )
    (net (code "45") (name "Net-(R24-Pad1)") (class "Default")
      (node (ref "R24") (pin "1") (pinfunction "1_1") (pintype "passive"))
      (node (ref "U$4") (pin "G") (pinfunction "G_G") (pintype "bidirectional"))
    )
    (net (code "46") (name "Net-(R30-Pad1)") (class "Default")
      (node (ref "R30") (pin "1") (pinfunction "1_1") (pintype "passive"))
      (node (ref "R31") (pin "2") (pinfunction "2_2") (pintype "passive"))
      (node (ref "S2") (pin "SW+") (pinfunction "SW+_SW+") (pintype "bidirectional"))
    )
    (net (code "47") (name "Net-(R32-Pad1)") (class "Default")
      (node (ref "R32") (pin "1") (pinfunction "1_1") (pintype "passive"))
      (node (ref "R33") (pin "2") (pinfunction "2_2") (pintype "passive"))
      (node (ref "S2") (pin "B") (pinfunction "B_B") (pintype "bidirectional"))
    )
    (net (code "48") (name "Net-(R34-Pad2)") (class "Default")
      (node (ref "R34") (pin "2") (pinfunction "2_2") (pintype "passive"))
      (node (ref "R35") (pin "2") (pinfunction "2_2") (pintype "passive"))
      (node (ref "S2") (pin "A") (pinfunction "A_A") (pintype "bidirectional"))
    )
    (net (code "49") (name "Net-(S0-S)") (class "Default")
      (node (ref "R7") (pin "1") (pinfunction "1_1") (pintype "passive"))
      (node (ref "R8") (pin "2") (pinfunction "2_2") (pintype "passive"))
      (node (ref "S0") (pin "1") (pinfunction "S_1") (pintype "passive"))
      (node (ref "S0") (pin "2") (pinfunction "S1_2") (pintype "passive"))
    )
    (net (code "50") (name "Net-(S1-S)") (class "Default")
      (node (ref "R28") (pin "1") (pinfunction "1_1") (pintype "passive"))
      (node (ref "R29") (pin "2") (pinfunction "2_2") (pintype "passive"))
      (node (ref "S1") (pin "1") (pinfunction "S_1") (pintype "passive"))
      (node (ref "S1") (pin "2") (pinfunction "S1_2") (pintype "passive"))
    )
    (net (code "51") (name "Net-(U$1-GPIO1)") (class "Default")
      (node (ref "R27") (pin "1") (pinfunction "1_1") (pintype "passive"))
      (node (ref "TH1") (pin "1") (pinfunction "1_1") (pintype "passive"))
      (node (ref "U$1") (pin "P$3") (pinfunction "GPIO1_P$3") (pintype "bidirectional"))
    )
    (net (code "52") (name "Net-(U$1-SENSE2-)") (class "Default")
      (node (ref "R12") (pin "2") (pinfunction "2_2") (pintype "passive"))
      (node (ref "U$1") (pin "P$16") (pinfunction "SENSE2-_P$16") (pintype "bidirectional"))
      (node (ref "U$4") (pin "D") (pinfunction "D_D") (pintype "bidirectional"))
      (node (ref "U$5") (pin "D") (pinfunction "D_D") (pintype "bidirectional"))
    )
    (net (code "53") (name "Net-(U$3-OUT0)") (class "Default")
      (node (ref "R17") (pin "1") (pinfunction "1_1") (pintype "passive"))
      (node (ref "U$3") (pin "3") (pinfunction "OUT0_3") (pintype "bidirectional"))
    )
    (net (code "54") (name "Net-(U$3-VDD)") (class "Default")
      (node (ref "C6") (pin "1") (pinfunction "1_1") (pintype "passive"))
      (node (ref "FB1") (pin "1") (pinfunction "1_1") (pintype "passive"))
      (node (ref "U$3") (pin "1") (pinfunction "VDD_1") (pintype "bidirectional"))
    )
    (net (code "55") (name "Net-(U$6-D)") (class "Default")
      (node (ref "D4") (pin "A") (pinfunction "A_A") (pintype "passive"))
      (node (ref "JP2") (pin "1") (pinfunction "1_1") (pintype "passive"))
      (node (ref "U$6") (pin "3") (pinfunction "D_3") (pintype "bidirectional"))
    )
    (net (code "56") (name "Net-(U1-PB6(XTAL1{slash}TOSC1))") (class "Default")
      (node (ref "C1") (pin "1") (pinfunction "1_1") (pintype "passive"))
      (node (ref "Q1") (pin "2") (pinfunction "2_2") (pintype "passive"))
      (node (ref "U1") (pin "9") (pinfunction "PB6(XTAL1/TOSC1)_9") (pintype "bidirectional"))
    )
    (net (code "57") (name "Net-(U1-PB7(XTAL2{slash}TOSC2))") (class "Default")
      (node (ref "C5") (pin "1") (pinfunction "1_1") (pintype "passive"))
      (node (ref "Q1") (pin "1") (pinfunction "1_1") (pintype "passive"))
      (node (ref "U1") (pin "10") (pinfunction "PB7(XTAL2/TOSC2)_10") (pintype "bidirectional"))
    )
    (net (code "58") (name "RESET") (class "Default")
      (node (ref "J2") (pin "5") (pinfunction "RESET_5") (pintype "passive"))
      (node (ref "R2") (pin "1") (pinfunction "1_1") (pintype "passive"))
      (node (ref "U1") (pin "1") (pinfunction "PC6(/RESET)_1") (pintype "bidirectional"))
    )
    (net (code "59") (name "RX") (class "Default")
      (node (ref "BR1") (pin "5") (pinfunction "URX_5") (pintype "bidirectional"))
      (node (ref "SV1") (pin "3") (pinfunction "3_3") (pintype "passive"))
      (node (ref "U1") (pin "3") (pinfunction "PD1(TXD)_3") (pintype "bidirectional"))
    )
    (net (code "60") (name "SCK") (class "Default")
      (node (ref "C15") (pin "1") (pinfunction "1_1") (pintype "passive"))
      (node (ref "J2") (pin "7") (pinfunction "SCK_7") (pintype "passive"))
      (node (ref "R34") (pin "1") (pinfunction "1_1") (pintype "passive"))
      (node (ref "U1") (pin "19") (pinfunction "PB5(SCK)_19") (pintype "bidirectional"))
    )
    (net (code "61") (name "SCL") (class "Default")
      (node (ref "R5") (pin "1") (pinfunction "1_1") (pintype "passive"))
      (node (ref "SV1") (pin "6") (pinfunction "6_6") (pintype "passive"))
      (node (ref "U$1") (pin "P$9") (pinfunction "SCL_P$9") (pintype "bidirectional"))
      (node (ref "U$3") (pin "7") (pinfunction "SCL_7") (pintype "bidirectional"))
      (node (ref "U1") (pin "28") (pinfunction "PC5(ADC5/SCL)_28") (pintype "bidirectional"))
    )
    (net (code "62") (name "SDA") (class "Default")
      (node (ref "R3") (pin "1") (pinfunction "1_1") (pintype "passive"))
      (node (ref "SV1") (pin "4") (pinfunction "4_4") (pintype "passive"))
      (node (ref "U$1") (pin "P$10") (pinfunction "SDAI_P$10") (pintype "bidirectional"))
      (node (ref "U$1") (pin "P$11") (pinfunction "SDAO_P$11") (pintype "bidirectional"))
      (node (ref "U$3") (pin "8") (pinfunction "SDA_8") (pintype "bidirectional"))
      (node (ref "U1") (pin "27") (pinfunction "PC4(ADC4/SDA)_27") (pintype "bidirectional"))
    )
    (net (code "63") (name "TX") (class "Default")
      (node (ref "BR1") (pin "6") (pinfunction "UTX_6") (pintype "bidirectional"))
      (node (ref "SV1") (pin "5") (pinfunction "5_5") (pintype "passive"))
      (node (ref "U1") (pin "2") (pinfunction "PD0(RXD)_2") (pintype "bidirectional"))
    )
    (net (code "64") (name "V+") (class "Default")
      (node (ref "R11") (pin "2") (pinfunction "2_2") (pintype "passive"))
      (node (ref "U$1") (pin "P$1") (pinfunction "SENSE1-_P$1") (pintype "bidirectional"))
      (node (ref "X1") (pin "P$2") (pinfunction "P$2_P$2") (pintype "bidirectional"))
    )
    (net (code "65") (name "V-") (class "Default")
      (node (ref "R12") (pin "1") (pinfunction "1_1") (pintype "passive"))
      (node (ref "U$1") (pin "P$15") (pinfunction "SENS2+_P$15") (pintype "bidirectional"))
      (node (ref "X1") (pin "P$3") (pinfunction "P$3_P$3") (pintype "bidirectional"))
    )
    (net (code "66") (name "VIN") (class "Default")
      (node (ref "R11") (pin "1") (pinfunction "1_1") (pintype "passive"))
      (node (ref "U$1") (pin "P$2") (pinfunction "SENSE1+_P$2") (pintype "bidirectional"))
      (node (ref "X1") (pin "P$1") (pinfunction "P$1_P$1") (pintype "bidirectional"))
    )
    (net (code "67") (name "V_USB") (class "Default")
      (node (ref "D6") (pin "A") (pinfunction "A_A") (pintype "passive"))
      (node (ref "J1") (pin "VBUS") (pinfunction "VBUS_VBUS") (pintype "power_in"))
    )
    (net (code "68") (name "unconnected-(BR1-GP2-Pad7)") (class "Default")
      (node (ref "BR1") (pin "7") (pinfunction "GP2_7") (pintype "bidirectional"))
    )
    (net (code "69") (name "unconnected-(BR1-GP3-Pad8)") (class "Default")
      (node (ref "BR1") (pin "8") (pinfunction "GP3_8") (pintype "bidirectional"))
    )
    (net (code "70") (name "unconnected-(BR1-RESET-Pad4)") (class "Default")
      (node (ref "BR1") (pin "4") (pinfunction "RESET_4") (pintype "bidirectional"))
    )
    (net (code "71") (name "unconnected-(BR1-SCL-Pad10)") (class "Default")
      (node (ref "BR1") (pin "10") (pinfunction "SCL_10") (pintype "bidirectional"))
    )
    (net (code "72") (name "unconnected-(BR1-SDA-Pad9)") (class "Default")
      (node (ref "BR1") (pin "9") (pinfunction "SDA_9") (pintype "bidirectional"))
    )
    (net (code "73") (name "unconnected-(J1-PadID)") (class "Default")
      (node (ref "J1") (pin "ID") (pinfunction "ID_ID") (pintype "bidirectional"))
    )
    (net (code "74") (name "unconnected-(J2-NC-Pad3)") (class "Default")
      (node (ref "J2") (pin "3") (pinfunction "NC_3") (pintype "no_connect"))
    )
    (net (code "75") (name "unconnected-(LCD1-DB0-Pad7)") (class "Default")
      (node (ref "LCD1") (pin "7") (pinfunction "DB0_7") (pintype "bidirectional"))
    )
    (net (code "76") (name "unconnected-(LCD1-DB1-Pad8)") (class "Default")
      (node (ref "LCD1") (pin "8") (pinfunction "DB1_8") (pintype "bidirectional"))
    )
    (net (code "77") (name "unconnected-(LCD1-DB2-Pad9)") (class "Default")
      (node (ref "LCD1") (pin "9") (pinfunction "DB2_9") (pintype "bidirectional"))
    )
    (net (code "78") (name "unconnected-(LCD1-DB3-Pad10)") (class "Default")
      (node (ref "LCD1") (pin "10") (pinfunction "DB3_10") (pintype "bidirectional"))
    )
    (net (code "79") (name "unconnected-(U$1-GPIO3-PadP$4)") (class "Default")
      (node (ref "U$1") (pin "P$4") (pinfunction "GPIO3_P$4") (pintype "bidirectional"))
    )
    (net (code "80") (name "unconnected-(U$3-LAT0-Pad6)") (class "Default")
      (node (ref "U$3") (pin "6") (pinfunction "LAT0_6") (pintype "bidirectional"))
    )
    (net (code "81") (name "unconnected-(U$3-NC-Pad4)") (class "Default")
      (node (ref "U$3") (pin "4") (pinfunction "NC_4") (pintype "bidirectional"))
    )
    (net (code "82") (name "unconnected-(U$3-VFRE0-Pad2)") (class "Default")
      (node (ref "U$3") (pin "2") (pinfunction "VFRE0_2") (pintype "bidirectional"))
    )
  )
)
